# Tahu.net
KiCad netlist of a schematic drawn in EAGLE
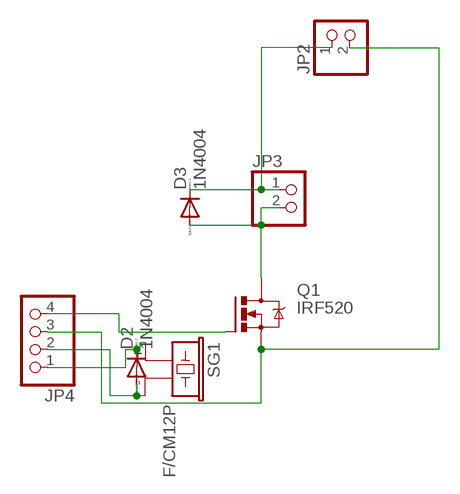
[diagram p0: schematic, sheet 1]

(export (version "E")
  (design (tool "Eeschema 10.0.6"))
  (components
    (comp (ref "D2")
      (value "1N4004")
      (footprint "eagle-import:DO41-10")
      (libsource (lib "eagle-import") (part "1N4004"))
    )
    (comp (ref "D3")
      (value "1N4004")
      (footprint "eagle-import:DO41-10")
      (libsource (lib "eagle-import") (part "1N4004"))
    )
    (comp (ref "JP2")
      (value "PINHD-1X2")
      (footprint "eagle-import:1X02")
      (libsource (lib "eagle-import") (part "PINHD-1X2"))
    )
    (comp (ref "JP3")
      (value "PINHD-1X2")
      (footprint "eagle-import:1X02")
      (libsource (lib "eagle-import") (part "PINHD-1X2"))
    )
    (comp (ref "JP4")
      (value "PINHD-1X4")
      (footprint "eagle-import:1X04")
      (libsource (lib "eagle-import") (part "PINHD-1X4"))
    )
    (comp (ref "Q1")
      (value "IRF520")
      (footprint "eagle-import:TO220BV")
      (libsource (lib "eagle-import") (part "IRF520"))
    )
    (comp (ref "SG1")
      (value "F/CM12P")
      (footprint "eagle-import:F_CM12P")
      (libsource (lib "eagle-import") (part "F/CM12P"))
    )
  )
  (nets
    (net (code "1") (name "Net-(D3-PadA)") (class "Default")
      (node (ref "D3") (pin "A") (pinfunction "A_A") (pintype "passive"))
      (node (ref "JP3") (pin "2") (pinfunction "2_2") (pintype "passive"))
      (node (ref "Q1") (pin "D") (pinfunction "D_D") (pintype "passive"))
    )
    (net (code "2") (name "Net-(D3-PadC)") (class "Default")
      (node (ref "D3") (pin "C") (pinfunction "C_C") (pintype "passive"))
      (node (ref "JP2") (pin "1") (pinfunction "1_1") (pintype "passive"))
      (node (ref "JP3") (pin "1") (pinfunction "1_1") (pintype "passive"))
    )
    (net (code "3") (name "Net-(JP2-Pad2)") (class "Default")
      (node (ref "JP2") (pin "2") (pinfunction "2_2") (pintype "passive"))
      (node (ref "JP4") (pin "3") (pinfunction "3_3") (pintype "passive"))
      (node (ref "Q1") (pin "S") (pinfunction "S_S") (pintype "passive"))
    )
    (net (code "4") (name "Net-(JP4-Pad4)") (class "Default")
      (node (ref "JP4") (pin "4") (pinfunction "4_4") (pintype "passive"))
      (node (ref "Q1") (pin "G") (pinfunction "G_G") (pintype "passive"))
    )
    (net (code "5") (name "Net-(SG1-1)") (class "Default")
      (node (ref "D2") (pin "C") (pinfunction "C_C") (pintype "passive"))
      (node (ref "JP4") (pin "1") (pinfunction "1_1") (pintype "passive"))
      (node (ref "SG1") (pin "+") (pinfunction "1_+") (pintype "passive"))
    )
    (net (code "6") (name "Net-(SG1-2)") (class "Default")
      (node (ref "D2") (pin "A") (pinfunction "A_A") (pintype "passive"))
      (node (ref "JP4") (pin "2") (pinfunction "2_2") (pintype "passive"))
      (node (ref "SG1") (pin "-") (pinfunction "2_-") (pintype "passive"))
    )
  )
)
